# BandpassedGainAmpSMT.net
KiCad netlist of a schematic drawn in EAGLE
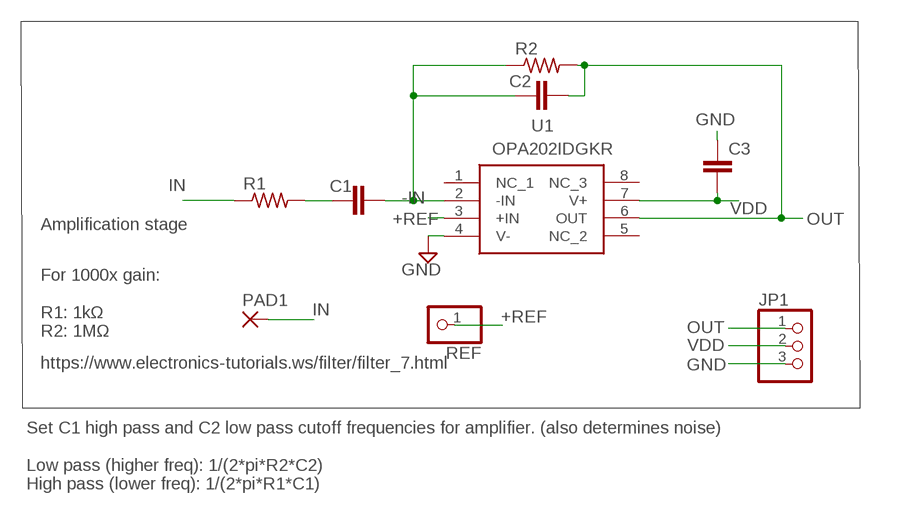
[diagram p0: schematic, sheet 1]

(export (version "E")
  (design (tool "Eeschema 10.0.6"))
  (components
    (comp (ref "C1")
      (value "C-EUC0402")
      (footprint "eagle-import:C0402")
      (libsource (lib "eagle-import") (part "C-EUC0402"))
    )
    (comp (ref "C2")
      (value "C-EUC0402")
      (footprint "eagle-import:C0402")
      (libsource (lib "eagle-import") (part "C-EUC0402"))
    )
    (comp (ref "C3")
      (value "C-EUC0402")
      (footprint "eagle-import:C0402")
      (libsource (lib "eagle-import") (part "C-EUC0402"))
    )
    (comp (ref "JP1")
      (value "PINHD-1X3")
      (footprint "eagle-import:1X03")
      (libsource (lib "eagle-import") (part "PINHD-1X3"))
    )
    (comp (ref "PAD1")
      (value "3,17/1,1")
      (footprint "eagle-import:3,17_1,1")
      (libsource (lib "eagle-import") (part "3,17/1,1"))
    )
    (comp (ref "R1")
      (value "R-US_R0402")
      (footprint "eagle-import:R0402")
      (libsource (lib "eagle-import") (part "R-US_R0402"))
    )
    (comp (ref "R2")
      (value "R-US_R0402")
      (footprint "eagle-import:R0402")
      (libsource (lib "eagle-import") (part "R-US_R0402"))
    )
    (comp (ref "REF")
      (value "PINHD-1X1")
      (footprint "eagle-import:1X01")
      (libsource (lib "eagle-import") (part "PINHD-1X1"))
    )
    (comp (ref "U1")
      (value "OPA202IDGKR")
      (footprint "eagle-import:SOP65P490X110-8N")
      (fields (field (name "MOUSER_PART_NUMBER") "595-OPA202IDGKR"))
      (libsource (lib "eagle-import") (part "OPA202IDGKR"))
    )
  )
  (nets
    (net (code "1") (name "/+REF") (class "Default")
      (node (ref "REF") (pin "1") (pinfunction "1_1") (pintype "passive"))
      (node (ref "U1") (pin "3") (pinfunction "+IN_3") (pintype "bidirectional"))
    )
    (net (code "2") (name "/-IN") (class "Default")
      (node (ref "C1") (pin "2") (pinfunction "2_2") (pintype "passive"))
      (node (ref "C2") (pin "1") (pinfunction "1_1") (pintype "passive"))
      (node (ref "R2") (pin "1") (pinfunction "1_1") (pintype "passive"))
      (node (ref "U1") (pin "2") (pinfunction "-IN_2") (pintype "bidirectional"))
    )
    (net (code "3") (name "/IN") (class "Default")
      (node (ref "PAD1") (pin "1") (pinfunction "P_1") (pintype "passive"))
      (node (ref "R1") (pin "1") (pinfunction "1_1") (pintype "passive"))
    )
    (net (code "4") (name "/OUT") (class "Default")
      (node (ref "C2") (pin "2") (pinfunction "2_2") (pintype "passive"))
      (node (ref "JP1") (pin "1") (pinfunction "1_1") (pintype "passive"))
      (node (ref "R2") (pin "2") (pinfunction "2_2") (pintype "passive"))
      (node (ref "U1") (pin "6") (pinfunction "OUT_6") (pintype "bidirectional"))
    )
    (net (code "5") (name "/VDD") (class "Default")
      (node (ref "C3") (pin "2") (pinfunction "2_2") (pintype "passive"))
      (node (ref "JP1") (pin "2") (pinfunction "2_2") (pintype "passive"))
      (node (ref "U1") (pin "7") (pinfunction "V+_7") (pintype "bidirectional"))
    )
    (net (code "6") (name "GND") (class "Default")
      (node (ref "C3") (pin "1") (pinfunction "1_1") (pintype "passive"))
      (node (ref "JP1") (pin "3") (pinfunction "3_3") (pintype "passive"))
      (node (ref "U1") (pin "4") (pinfunction "V-_4") (pintype "bidirectional"))
    )
    (net (code "7") (name "Net-(C1-Pad1)") (class "Default")
      (node (ref "C1") (pin "1") (pinfunction "1_1") (pintype "passive"))
      (node (ref "R1") (pin "2") (pinfunction "2_2") (pintype "passive"))
    )
    (net (code "8") (name "unconnected-(U1-NC_1-Pad1)") (class "Default")
      (node (ref "U1") (pin "1") (pinfunction "NC_1_1") (pintype "bidirectional"))
    )
    (net (code "9") (name "unconnected-(U1-NC_2-Pad5)") (class "Default")
      (node (ref "U1") (pin "5") (pinfunction "NC_2_5") (pintype "bidirectional"))
    )
    (net (code "10") (name "unconnected-(U1-NC_3-Pad8)") (class "Default")
      (node (ref "U1") (pin "8") (pinfunction "NC_3_8") (pintype "bidirectional"))
    )
  )
)
